# FilterSupplySingle.net
KiCad netlist of a schematic drawn in EAGLE
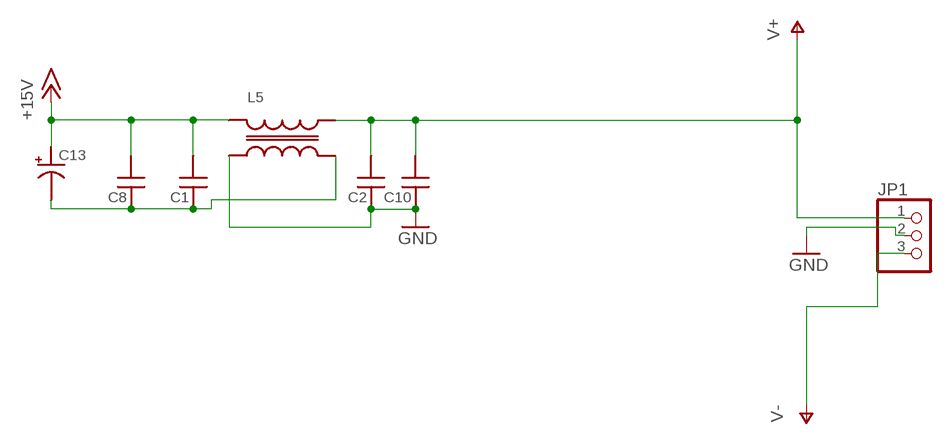
[diagram p0: schematic, sheet 1]

(export (version "E")
  (design (tool "Eeschema 10.0.6"))
  (components
    (comp (ref "C1")
      (value "C_MLCC_SMDCMLCC_0805")
      (footprint "eagle-import:C_MLCC_0805")
      (libsource (lib "eagle-import") (part "C_MLCC_SMDCMLCC_0805"))
    )
    (comp (ref "C2")
      (value "C_MLCC_SMDCMLCC_0805")
      (footprint "eagle-import:C_MLCC_0805")
      (libsource (lib "eagle-import") (part "C_MLCC_SMDCMLCC_0805"))
    )
    (comp (ref "C8")
      (value "C_MLCC_SMDCMLCC_0603")
      (footprint "eagle-import:C_MLCC_0603")
      (libsource (lib "eagle-import") (part "C_MLCC_SMDCMLCC_0603"))
    )
    (comp (ref "C10")
      (value "C_MLCC_SMDCMLCC_0603")
      (footprint "eagle-import:C_MLCC_0603")
      (libsource (lib "eagle-import") (part "C_MLCC_SMDCMLCC_0603"))
    )
    (comp (ref "C13")
      (value "C_POL_SMDF")
      (footprint "eagle-import:PANASONIC_F")
      (libsource (lib "eagle-import") (part "C_POL_SMDF"))
    )
    (comp (ref "JP1")
      (value "PINHD-1X3")
      (footprint "eagle-import:1X03")
      (libsource (lib "eagle-import") (part "PINHD-1X3"))
    )
    (comp (ref "L5")
      (value "MSD7342")
      (footprint "eagle-import:MSD7342")
      (libsource (lib "eagle-import") (part "MSD7342"))
    )
  )
  (nets
    (net (code "1") (name "+15V") (class "Default")
      (node (ref "C1") (pin "P$2") (pinfunction "2_P$2") (pintype "passive"))
      (node (ref "C13") (pin "+") (pinfunction "+_+") (pintype "passive"))
      (node (ref "C8") (pin "P$2") (pinfunction "2_P$2") (pintype "passive"))
      (node (ref "L5") (pin "2") (pinfunction "2_2") (pintype "passive"))
    )
    (net (code "2") (name "GND") (class "Default")
      (node (ref "C10") (pin "P$1") (pinfunction "1_P$1") (pintype "passive"))
      (node (ref "C2") (pin "P$1") (pinfunction "1_P$1") (pintype "passive"))
      (node (ref "JP1") (pin "2") (pinfunction "2_2") (pintype "passive"))
      (node (ref "L5") (pin "1") (pinfunction "1_1") (pintype "passive"))
    )
    (net (code "3") (name "Net-(C1-1)") (class "Default")
      (node (ref "C1") (pin "P$1") (pinfunction "1_P$1") (pintype "passive"))
      (node (ref "C13") (pin "-") (pinfunction "-_-") (pintype "passive"))
      (node (ref "C8") (pin "P$1") (pinfunction "1_P$1") (pintype "passive"))
      (node (ref "L5") (pin "3") (pinfunction "3_3") (pintype "passive"))
    )
    (net (code "4") (name "V+") (class "Default")
      (node (ref "C10") (pin "P$2") (pinfunction "2_P$2") (pintype "passive"))
      (node (ref "C2") (pin "P$2") (pinfunction "2_P$2") (pintype "passive"))
      (node (ref "JP1") (pin "1") (pinfunction "1_1") (pintype "passive"))
      (node (ref "L5") (pin "4") (pinfunction "4_4") (pintype "passive"))
    )
    (net (code "5") (name "V-") (class "Default")
      (node (ref "JP1") (pin "3") (pinfunction "3_3") (pintype "passive"))
    )
  )
)
